# Sheet1.net
KiCad netlist of a schematic drawn in Altium Designer
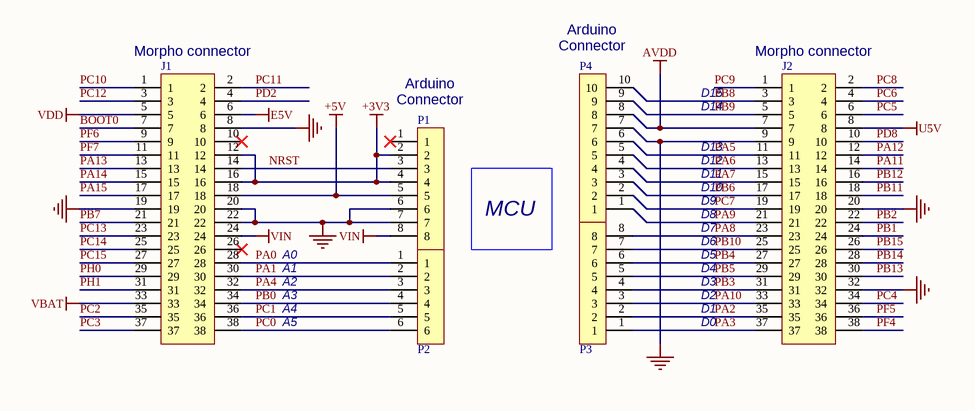
[diagram p0: Sheet1.SchDoc]

(export (version "E")
  (design (tool "Eeschema 10.0.6"))
  (components
    (comp (ref "J1")
      (value "CES-119-02-T-D")
      (footprint "PcbLib1:SAMTEC_CES-119-02-T-D")
      (description "Headers & Wire Housings .100\" Closed Entry Low Profile Socket Strip, 2x19")
      (libsource (lib "Schlib1") (part "CES-119-02-T-D"))
    )
    (comp (ref "J2")
      (value "CES-119-02-T-D")
      (footprint "PcbLib1:SAMTEC_CES-119-02-T-D")
      (description "Headers & Wire Housings .100\" Closed Entry Low Profile Socket Strip, 2x19")
      (libsource (lib "Schlib1") (part "CES-119-02-T-D"))
    )
    (comp (ref "P1")
      (value "61300811121")
      (footprint "PcbLib1:HDRV8W64P0X254_1X8_2032X254X854P")
      (description "Headers & Wire Housings WR-PHD 2.54mm Hdr 8P Single Str Gold")
      (fields (field (name "MOUSER PART NUMBER") "710-61300811121"))
      (libsource (lib "Schlib1") (part "61300811121"))
    )
    (comp (ref "P2")
      (value "10129378-906001BLF")
      (footprint "PcbLib1:10129378906001BLF")
      (description "Headers & Wire Housings ECONOSTIK HEADER SR VT TH 1X6")
      (libsource (lib "Schlib1") (part "10129378-906001BLF"))
    )
    (comp (ref "P3")
      (value "61300811121")
      (footprint "PcbLib1:HDRV8W64P0X254_1X8_2032X254X854P")
      (description "Headers & Wire Housings WR-PHD 2.54mm Hdr 8P Single Str Gold")
      (fields (field (name "MOUSER PART NUMBER") "710-61300811121"))
      (libsource (lib "") (part "61300811121_1"))
    )
    (comp (ref "P4")
      (value "TSW-110-07-G-S")
      (footprint "PcbLib1:HDRV10W64P0X254_1X10_2540X254X838P")
      (description "Headers & Wire Housings Classic PCB Header Strips, 0.100\" pitch")
      (fields (field (name "MOUSER PART NUMBER") "200-TSW11007GS"))
      (libsource (lib "Schlib1") (part "TSW-110-07-G-S"))
    )
  )
  (nets
    (net (code "1") (name "+3V3") (class "Default")
      (node (ref "J1") (pin "12") (pinfunction "12_12") (pintype "passive"))
      (node (ref "J1") (pin "16") (pinfunction "16_16") (pintype "passive"))
      (node (ref "P1") (pin "2") (pinfunction "2_2") (pintype "passive"))
      (node (ref "P1") (pin "4") (pinfunction "4_4") (pintype "passive"))
    )
    (net (code "2") (name "+5V") (class "Default")
      (node (ref "J1") (pin "18") (pinfunction "18_18") (pintype "passive"))
      (node (ref "P1") (pin "5") (pinfunction "5_5") (pintype "passive"))
    )
    (net (code "3") (name "/BOOT0") (class "Default")
      (node (ref "J1") (pin "7") (pinfunction "7_7") (pintype "passive"))
    )
    (net (code "4") (name "/NRST") (class "Default")
      (node (ref "J1") (pin "14") (pinfunction "14_14") (pintype "passive"))
      (node (ref "P1") (pin "3") (pinfunction "3_3") (pintype "passive"))
    )
    (net (code "5") (name "/PA0") (class "Default")
      (node (ref "J1") (pin "28") (pinfunction "28_28") (pintype "passive"))
      (node (ref "P2") (pin "1") (pinfunction "1_1") (pintype "passive"))
    )
    (net (code "6") (name "/PA1") (class "Default")
      (node (ref "J1") (pin "30") (pinfunction "30_30") (pintype "passive"))
      (node (ref "P2") (pin "2") (pinfunction "2_2") (pintype "passive"))
    )
    (net (code "7") (name "/PA2") (class "Default")
      (node (ref "J2") (pin "35") (pinfunction "35_35") (pintype "passive"))
      (node (ref "P3") (pin "2") (pinfunction "2_2") (pintype "passive"))
    )
    (net (code "8") (name "/PA3") (class "Default")
      (node (ref "J2") (pin "37") (pinfunction "37_37") (pintype "passive"))
      (node (ref "P3") (pin "1") (pinfunction "1_1") (pintype "passive"))
    )
    (net (code "9") (name "/PA4") (class "Default")
      (node (ref "J1") (pin "32") (pinfunction "32_32") (pintype "passive"))
      (node (ref "P2") (pin "3") (pinfunction "3_3") (pintype "passive"))
    )
    (net (code "10") (name "/PA5") (class "Default")
      (node (ref "J2") (pin "11") (pinfunction "11_11") (pintype "passive"))
      (node (ref "P4") (pin "6") (pinfunction "6_6") (pintype "passive"))
    )
    (net (code "11") (name "/PA6") (class "Default")
      (node (ref "J2") (pin "13") (pinfunction "13_13") (pintype "passive"))
      (node (ref "P4") (pin "5") (pinfunction "5_5") (pintype "passive"))
    )
    (net (code "12") (name "/PA7") (class "Default")
      (node (ref "J2") (pin "15") (pinfunction "15_15") (pintype "passive"))
      (node (ref "P4") (pin "4") (pinfunction "4_4") (pintype "passive"))
    )
    (net (code "13") (name "/PA8") (class "Default")
      (node (ref "J2") (pin "23") (pinfunction "23_23") (pintype "passive"))
      (node (ref "P3") (pin "8") (pinfunction "8_8") (pintype "passive"))
    )
    (net (code "14") (name "/PA9") (class "Default")
      (node (ref "J2") (pin "21") (pinfunction "21_21") (pintype "passive"))
      (node (ref "P4") (pin "1") (pinfunction "1_1") (pintype "passive"))
    )
    (net (code "15") (name "/PA10") (class "Default")
      (node (ref "J2") (pin "33") (pinfunction "33_33") (pintype "passive"))
      (node (ref "P3") (pin "3") (pinfunction "3_3") (pintype "passive"))
    )
    (net (code "16") (name "/PA11") (class "Default")
      (node (ref "J2") (pin "14") (pinfunction "14_14") (pintype "passive"))
    )
    (net (code "17") (name "/PA12") (class "Default")
      (node (ref "J2") (pin "12") (pinfunction "12_12") (pintype "passive"))
    )
    (net (code "18") (name "/PA13") (class "Default")
      (node (ref "J1") (pin "13") (pinfunction "13_13") (pintype "passive"))
    )
    (net (code "19") (name "/PA14") (class "Default")
      (node (ref "J1") (pin "15") (pinfunction "15_15") (pintype "passive"))
    )
    (net (code "20") (name "/PA15") (class "Default")
      (node (ref "J1") (pin "17") (pinfunction "17_17") (pintype "passive"))
    )
    (net (code "21") (name "/PB0") (class "Default")
      (node (ref "J1") (pin "34") (pinfunction "34_34") (pintype "passive"))
      (node (ref "P2") (pin "4") (pinfunction "4_4") (pintype "passive"))
    )
    (net (code "22") (name "/PB1") (class "Default")
      (node (ref "J2") (pin "24") (pinfunction "24_24") (pintype "passive"))
    )
    (net (code "23") (name "/PB2") (class "Default")
      (node (ref "J2") (pin "22") (pinfunction "22_22") (pintype "passive"))
    )
    (net (code "24") (name "/PB3") (class "Default")
      (node (ref "J2") (pin "31") (pinfunction "31_31") (pintype "passive"))
      (node (ref "P3") (pin "4") (pinfunction "4_4") (pintype "passive"))
    )
    (net (code "25") (name "/PB4") (class "Default")
      (node (ref "J2") (pin "27") (pinfunction "27_27") (pintype "passive"))
      (node (ref "P3") (pin "6") (pinfunction "6_6") (pintype "passive"))
    )
    (net (code "26") (name "/PB5") (class "Default")
      (node (ref "J2") (pin "29") (pinfunction "29_29") (pintype "passive"))
      (node (ref "P3") (pin "5") (pinfunction "5_5") (pintype "passive"))
    )
    (net (code "27") (name "/PB6") (class "Default")
      (node (ref "J2") (pin "17") (pinfunction "17_17") (pintype "passive"))
      (node (ref "P4") (pin "3") (pinfunction "3_3") (pintype "passive"))
    )
    (net (code "28") (name "/PB7") (class "Default")
      (node (ref "J1") (pin "21") (pinfunction "21_21") (pintype "passive"))
    )
    (net (code "29") (name "/PB8") (class "Default")
      (node (ref "J2") (pin "3") (pinfunction "3_3") (pintype "passive"))
      (node (ref "P4") (pin "10") (pinfunction "10_10") (pintype "passive"))
    )
    (net (code "30") (name "/PB9") (class "Default")
      (node (ref "J2") (pin "5") (pinfunction "5_5") (pintype "passive"))
      (node (ref "P4") (pin "9") (pinfunction "9_9") (pintype "passive"))
    )
    (net (code "31") (name "/PB10") (class "Default")
      (node (ref "J2") (pin "25") (pinfunction "25_25") (pintype "passive"))
      (node (ref "P3") (pin "7") (pinfunction "7_7") (pintype "passive"))
    )
    (net (code "32") (name "/PB11") (class "Default")
      (node (ref "J2") (pin "18") (pinfunction "18_18") (pintype "passive"))
    )
    (net (code "33") (name "/PB12") (class "Default")
      (node (ref "J2") (pin "16") (pinfunction "16_16") (pintype "passive"))
    )
    (net (code "34") (name "/PB13") (class "Default")
      (node (ref "J2") (pin "30") (pinfunction "30_30") (pintype "passive"))
    )
    (net (code "35") (name "/PB14") (class "Default")
      (node (ref "J2") (pin "28") (pinfunction "28_28") (pintype "passive"))
    )
    (net (code "36") (name "/PB15") (class "Default")
      (node (ref "J2") (pin "26") (pinfunction "26_26") (pintype "passive"))
    )
    (net (code "37") (name "/PC0") (class "Default")
      (node (ref "J1") (pin "38") (pinfunction "38_38") (pintype "passive"))
      (node (ref "P2") (pin "6") (pinfunction "6_6") (pintype "passive"))
    )
    (net (code "38") (name "/PC1") (class "Default")
      (node (ref "J1") (pin "36") (pinfunction "36_36") (pintype "passive"))
      (node (ref "P2") (pin "5") (pinfunction "5_5") (pintype "passive"))
    )
    (net (code "39") (name "/PC2") (class "Default")
      (node (ref "J1") (pin "35") (pinfunction "35_35") (pintype "passive"))
    )
    (net (code "40") (name "/PC3") (class "Default")
      (node (ref "J1") (pin "37") (pinfunction "37_37") (pintype "passive"))
    )
    (net (code "41") (name "/PC4") (class "Default")
      (node (ref "J2") (pin "34") (pinfunction "34_34") (pintype "passive"))
    )
    (net (code "42") (name "/PC5") (class "Default")
      (node (ref "J2") (pin "6") (pinfunction "6_6") (pintype "passive"))
    )
    (net (code "43") (name "/PC6") (class "Default")
      (node (ref "J2") (pin "4") (pinfunction "4_4") (pintype "passive"))
    )
    (net (code "44") (name "/PC7") (class "Default")
      (node (ref "J2") (pin "19") (pinfunction "19_19") (pintype "passive"))
      (node (ref "P4") (pin "2") (pinfunction "2_2") (pintype "passive"))
    )
    (net (code "45") (name "/PC8") (class "Default")
      (node (ref "J2") (pin "2") (pinfunction "2_2") (pintype "passive"))
    )
    (net (code "46") (name "/PC9") (class "Default")
      (node (ref "J2") (pin "1") (pinfunction "1_1") (pintype "passive"))
    )
    (net (code "47") (name "/PC10") (class "Default")
      (node (ref "J1") (pin "1") (pinfunction "1_1") (pintype "passive"))
    )
    (net (code "48") (name "/PC11") (class "Default")
      (node (ref "J1") (pin "2") (pinfunction "2_2") (pintype "passive"))
    )
    (net (code "49") (name "/PC12") (class "Default")
      (node (ref "J1") (pin "3") (pinfunction "3_3") (pintype "passive"))
    )
    (net (code "50") (name "/PC13") (class "Default")
      (node (ref "J1") (pin "23") (pinfunction "23_23") (pintype "passive"))
    )
    (net (code "51") (name "/PC14") (class "Default")
      (node (ref "J1") (pin "25") (pinfunction "25_25") (pintype "passive"))
    )
    (net (code "52") (name "/PC15") (class "Default")
      (node (ref "J1") (pin "27") (pinfunction "27_27") (pintype "passive"))
    )
    (net (code "53") (name "/PD2") (class "Default")
      (node (ref "J1") (pin "4") (pinfunction "4_4") (pintype "passive"))
    )
    (net (code "54") (name "/PD8") (class "Default")
      (node (ref "J2") (pin "10") (pinfunction "10_10") (pintype "passive"))
    )
    (net (code "55") (name "/PF4") (class "Default")
      (node (ref "J2") (pin "38") (pinfunction "38_38") (pintype "passive"))
    )
    (net (code "56") (name "/PF5") (class "Default")
      (node (ref "J2") (pin "36") (pinfunction "36_36") (pintype "passive"))
    )
    (net (code "57") (name "/PF6") (class "Default")
      (node (ref "J1") (pin "9") (pinfunction "9_9") (pintype "passive"))
    )
    (net (code "58") (name "/PF7") (class "Default")
      (node (ref "J1") (pin "11") (pinfunction "11_11") (pintype "passive"))
    )
    (net (code "59") (name "/PH0") (class "Default")
      (node (ref "J1") (pin "29") (pinfunction "29_29") (pintype "passive"))
    )
    (net (code "60") (name "/PH1") (class "Default")
      (node (ref "J1") (pin "31") (pinfunction "31_31") (pintype "passive"))
    )
    (net (code "61") (name "AVDD") (class "Default")
      (node (ref "J2") (pin "7") (pinfunction "7_7") (pintype "passive"))
      (node (ref "P4") (pin "8") (pinfunction "8_8") (pintype "passive"))
    )
    (net (code "62") (name "E5V") (class "Default")
      (node (ref "J1") (pin "6") (pinfunction "6_6") (pintype "passive"))
    )
    (net (code "63") (name "GND") (class "Default")
      (node (ref "J1") (pin "19") (pinfunction "19_19") (pintype "passive"))
      (node (ref "J1") (pin "20") (pinfunction "20_20") (pintype "passive"))
      (node (ref "J1") (pin "22") (pinfunction "22_22") (pintype "passive"))
      (node (ref "J1") (pin "8") (pinfunction "8_8") (pintype "passive"))
      (node (ref "J2") (pin "20") (pinfunction "20_20") (pintype "passive"))
      (node (ref "J2") (pin "32") (pinfunction "32_32") (pintype "passive"))
      (node (ref "J2") (pin "9") (pinfunction "9_9") (pintype "passive"))
      (node (ref "P1") (pin "6") (pinfunction "6_6") (pintype "passive"))
      (node (ref "P1") (pin "7") (pinfunction "7_7") (pintype "passive"))
      (node (ref "P4") (pin "7") (pinfunction "7_7") (pintype "passive"))
    )
    (net (code "64") (name "U5V") (class "Default")
      (node (ref "J2") (pin "8") (pinfunction "8_8") (pintype "passive"))
    )
    (net (code "65") (name "VBAT") (class "Default")
      (node (ref "J1") (pin "33") (pinfunction "33_33") (pintype "passive"))
    )
    (net (code "66") (name "VDD") (class "Default")
      (node (ref "J1") (pin "5") (pinfunction "5_5") (pintype "passive"))
    )
    (net (code "67") (name "VIN") (class "Default")
      (node (ref "J1") (pin "24") (pinfunction "24_24") (pintype "passive"))
      (node (ref "P1") (pin "8") (pinfunction "8_8") (pintype "passive"))
    )
    (net (code "68") (name "unconnected-(J1-Pad10)") (class "Default")
      (node (ref "J1") (pin "10") (pinfunction "10_10") (pintype "passive+no_connect"))
    )
    (net (code "69") (name "unconnected-(J1-Pad26)") (class "Default")
      (node (ref "J1") (pin "26") (pinfunction "26_26") (pintype "passive+no_connect"))
    )
    (net (code "70") (name "unconnected-(P1-Pad1)") (class "Default")
      (node (ref "P1") (pin "1") (pinfunction "1_1") (pintype "passive+no_connect"))
    )
  )
)
